# slave-relay-v1.net
KiCad netlist of a schematic drawn in EAGLE
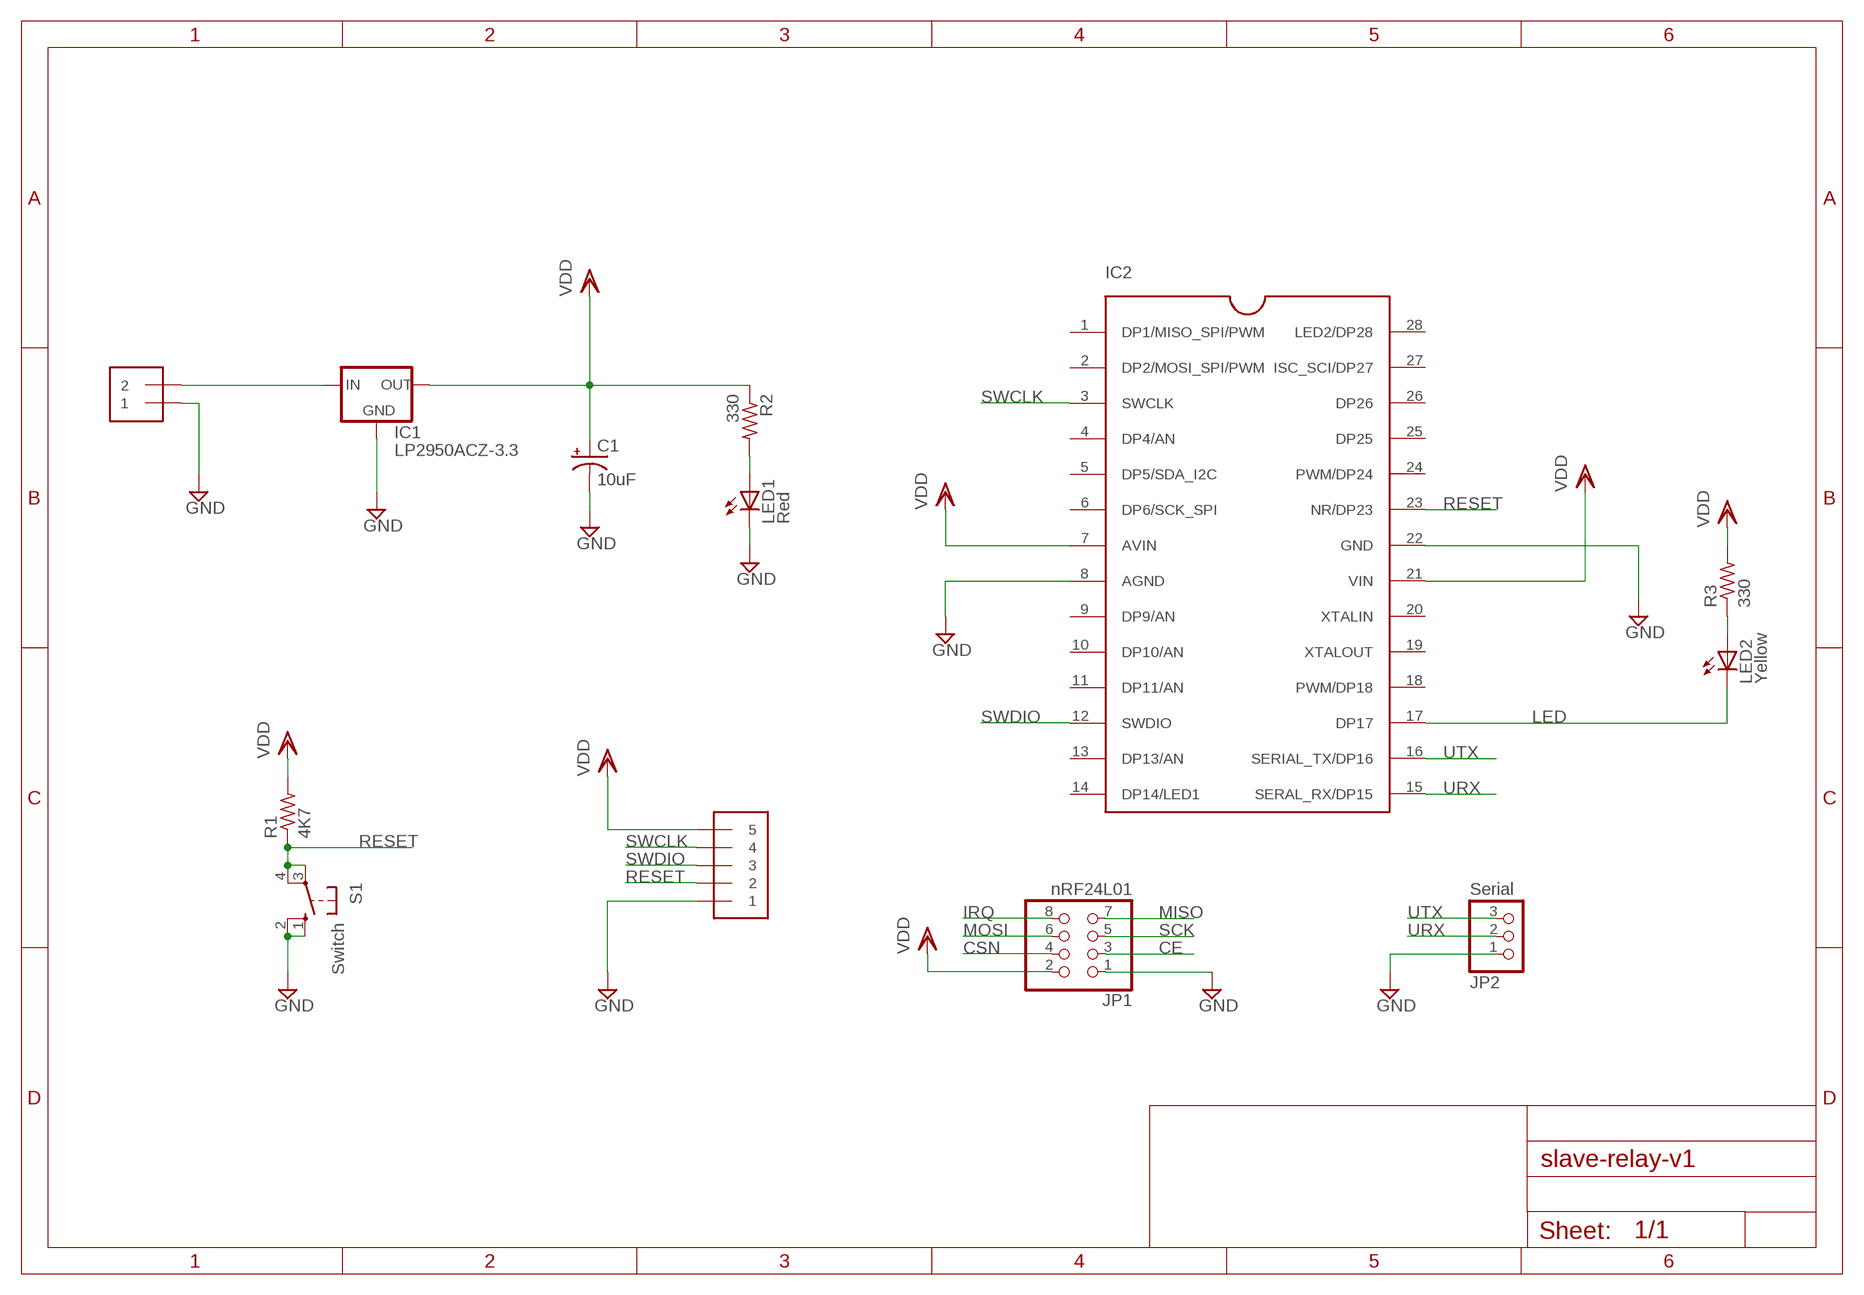
[diagram p0: schematic, sheet 1]

(export (version "E")
  (design (tool "Eeschema 10.0.6"))
  (components
    (comp (ref "C1")
      (value "10uF")
      (footprint "eagle-import:E2,5-7")
      (libsource (lib "eagle-import") (part "CPOL-USE2.5-7"))
    )
    (comp (ref "IC1")
      (value "LP2950ACZ-3.3")
      (footprint "eagle-import:TO92")
      (libsource (lib "eagle-import") (part "LP2950?ACZ-3.3"))
    )
    (comp (ref "IC2")
      (value "LPC1114FN28")
      (footprint "eagle-import:DIP28")
      (libsource (lib "eagle-import") (part "LPC1114FN28"))
    )
    (comp (ref "J1")
      (value "1X2-3.5MM")
      (footprint "eagle-import:1X2-3.5MM")
      (libsource (lib "eagle-import") (part "1X2-3.5MM"))
    )
    (comp (ref "J2")
      (value "SWD Debug")
      (footprint "eagle-import:1X05-3.5MM")
      (libsource (lib "eagle-import") (part "1X5"))
    )
    (comp (ref "JP1")
      (value "nRF24L01")
      (footprint "eagle-import:2X04")
      (libsource (lib "eagle-import") (part "PINHD-2X4"))
    )
    (comp (ref "JP2")
      (value "Serial")
      (footprint "eagle-import:1X03")
      (libsource (lib "eagle-import") (part "PINHD-1X3"))
    )
    (comp (ref "LED1")
      (value "Red")
      (footprint "eagle-import:LED5MM")
      (libsource (lib "eagle-import") (part "LED5MM"))
    )
    (comp (ref "LED2")
      (value "Yellow")
      (footprint "eagle-import:LED5MM")
      (libsource (lib "eagle-import") (part "LED5MM"))
    )
    (comp (ref "R1")
      (value "4K7")
      (footprint "eagle-import:0805-THM")
      (libsource (lib "eagle-import") (part "FLIPFLOP-RES"))
    )
    (comp (ref "R2")
      (value "330")
      (footprint "eagle-import:0805-THM")
      (libsource (lib "eagle-import") (part "FLIPFLOP-RES"))
    )
    (comp (ref "R3")
      (value "330")
      (footprint "eagle-import:0805-THM")
      (libsource (lib "eagle-import") (part "FLIPFLOP-RES"))
    )
    (comp (ref "S1")
      (value "Switch")
      (footprint "eagle-import:B3F-40XX")
      (fields (field (name "MF") "OMRON COMPONENTS USA") (field (name "MPN") "B3F-4000"))
      (libsource (lib "eagle-import") (part "40-XX"))
    )
  )
  (nets
    (net (code "1") (name "/CE") (class "Default")
      (node (ref "JP1") (pin "3") (pinfunction "3_3") (pintype "passive"))
    )
    (net (code "2") (name "/CSN") (class "Default")
      (node (ref "JP1") (pin "4") (pinfunction "4_4") (pintype "passive"))
    )
    (net (code "3") (name "/IRQ") (class "Default")
      (node (ref "JP1") (pin "8") (pinfunction "8_8") (pintype "passive"))
    )
    (net (code "4") (name "/LED") (class "Default")
      (node (ref "IC2") (pin "17") (pinfunction "DP17_17") (pintype "bidirectional"))
      (node (ref "LED2") (pin "K") (pinfunction "C_K") (pintype "passive"))
    )
    (net (code "5") (name "/MISO") (class "Default")
      (node (ref "JP1") (pin "7") (pinfunction "7_7") (pintype "passive"))
    )
    (net (code "6") (name "/MOSI") (class "Default")
      (node (ref "JP1") (pin "6") (pinfunction "6_6") (pintype "passive"))
    )
    (net (code "7") (name "/RESET") (class "Default")
      (node (ref "IC2") (pin "23") (pinfunction "NR/DP23_23") (pintype "bidirectional"))
      (node (ref "J2") (pin "2") (pinfunction "2_2") (pintype "passive"))
      (node (ref "R1") (pin "1") (pinfunction "1_1") (pintype "passive"))
      (node (ref "S1") (pin "3") (pinfunction "P_3") (pintype "passive"))
      (node (ref "S1") (pin "4") (pinfunction "P1_4") (pintype "passive"))
    )
    (net (code "8") (name "/SCK") (class "Default")
      (node (ref "JP1") (pin "5") (pinfunction "5_5") (pintype "passive"))
    )
    (net (code "9") (name "/SWCLK") (class "Default")
      (node (ref "IC2") (pin "3") (pinfunction "SWCLK_3") (pintype "bidirectional"))
      (node (ref "J2") (pin "4") (pinfunction "4_4") (pintype "passive"))
    )
    (net (code "10") (name "/SWDIO") (class "Default")
      (node (ref "IC2") (pin "12") (pinfunction "SWDIO_12") (pintype "bidirectional"))
      (node (ref "J2") (pin "3") (pinfunction "3_3") (pintype "passive"))
    )
    (net (code "11") (name "/URX") (class "Default")
      (node (ref "IC2") (pin "15") (pinfunction "SERAL_RX/DP15_15") (pintype "bidirectional"))
      (node (ref "JP2") (pin "2") (pinfunction "2_2") (pintype "passive"))
    )
    (net (code "12") (name "/UTX") (class "Default")
      (node (ref "IC2") (pin "16") (pinfunction "SERIAL_TX/DP16_16") (pintype "bidirectional"))
      (node (ref "JP2") (pin "3") (pinfunction "3_3") (pintype "passive"))
    )
    (net (code "13") (name "GND") (class "Default")
      (node (ref "C1") (pin "-") (pinfunction "-_-") (pintype "passive"))
      (node (ref "IC1") (pin "2") (pinfunction "GND_2") (pintype "input"))
      (node (ref "IC2") (pin "22") (pinfunction "GND_22") (pintype "power_in"))
      (node (ref "IC2") (pin "8") (pinfunction "AGND_8") (pintype "power_in"))
      (node (ref "J1") (pin "1") (pinfunction "1_1") (pintype "passive"))
      (node (ref "J2") (pin "1") (pinfunction "1_1") (pintype "passive"))
      (node (ref "JP1") (pin "1") (pinfunction "1_1") (pintype "passive"))
      (node (ref "JP2") (pin "1") (pinfunction "1_1") (pintype "passive"))
      (node (ref "LED1") (pin "K") (pinfunction "C_K") (pintype "passive"))
      (node (ref "S1") (pin "1") (pinfunction "S_1") (pintype "passive"))
      (node (ref "S1") (pin "2") (pinfunction "S1_2") (pintype "passive"))
    )
    (net (code "14") (name "Net-(IC1-IN)") (class "Default")
      (node (ref "IC1") (pin "3") (pinfunction "IN_3") (pintype "input"))
      (node (ref "J1") (pin "2") (pinfunction "2_2") (pintype "passive"))
    )
    (net (code "15") (name "Net-(LED1-PadA)") (class "Default")
      (node (ref "LED1") (pin "A") (pinfunction "A_A") (pintype "passive"))
      (node (ref "R2") (pin "2") (pinfunction "2_2") (pintype "passive"))
    )
    (net (code "16") (name "Net-(LED2-PadA)") (class "Default")
      (node (ref "LED2") (pin "A") (pinfunction "A_A") (pintype "passive"))
      (node (ref "R3") (pin "1") (pinfunction "1_1") (pintype "passive"))
    )
    (net (code "17") (name "VDD") (class "Default")
      (node (ref "C1") (pin "+") (pinfunction "+_+") (pintype "passive"))
      (node (ref "IC1") (pin "1") (pinfunction "OUT_1") (pintype "passive"))
      (node (ref "IC2") (pin "21") (pinfunction "VIN_21") (pintype "power_in"))
      (node (ref "IC2") (pin "7") (pinfunction "AVIN_7") (pintype "power_in"))
      (node (ref "J2") (pin "5") (pinfunction "5_5") (pintype "passive"))
      (node (ref "JP1") (pin "2") (pinfunction "2_2") (pintype "passive"))
      (node (ref "R1") (pin "2") (pinfunction "2_2") (pintype "passive"))
      (node (ref "R2") (pin "1") (pinfunction "1_1") (pintype "passive"))
      (node (ref "R3") (pin "2") (pinfunction "2_2") (pintype "passive"))
    )
    (net (code "18") (name "unconnected-(IC2-DP1{slash}MISO_SPI{slash}PWM-Pad1)") (class "Default")
      (node (ref "IC2") (pin "1") (pinfunction "DP1/MISO_SPI/PWM_1") (pintype "bidirectional"))
    )
    (net (code "19") (name "unconnected-(IC2-DP2{slash}MOSI_SPI{slash}PWM-Pad2)") (class "Default")
      (node (ref "IC2") (pin "2") (pinfunction "DP2/MOSI_SPI/PWM_2") (pintype "bidirectional"))
    )
    (net (code "20") (name "unconnected-(IC2-DP4{slash}AN-Pad4)") (class "Default")
      (node (ref "IC2") (pin "4") (pinfunction "DP4/AN_4") (pintype "bidirectional"))
    )
    (net (code "21") (name "unconnected-(IC2-DP5{slash}SDA_I2C-Pad5)") (class "Default")
      (node (ref "IC2") (pin "5") (pinfunction "DP5/SDA_I2C_5") (pintype "bidirectional"))
    )
    (net (code "22") (name "unconnected-(IC2-DP6{slash}SCK_SPI-Pad6)") (class "Default")
      (node (ref "IC2") (pin "6") (pinfunction "DP6/SCK_SPI_6") (pintype "bidirectional"))
    )
    (net (code "23") (name "unconnected-(IC2-DP9{slash}AN-Pad9)") (class "Default")
      (node (ref "IC2") (pin "9") (pinfunction "DP9/AN_9") (pintype "bidirectional"))
    )
    (net (code "24") (name "unconnected-(IC2-DP10{slash}AN-Pad10)") (class "Default")
      (node (ref "IC2") (pin "10") (pinfunction "DP10/AN_10") (pintype "bidirectional"))
    )
    (net (code "25") (name "unconnected-(IC2-DP11{slash}AN-Pad11)") (class "Default")
      (node (ref "IC2") (pin "11") (pinfunction "DP11/AN_11") (pintype "bidirectional"))
    )
    (net (code "26") (name "unconnected-(IC2-DP13{slash}AN-Pad13)") (class "Default")
      (node (ref "IC2") (pin "13") (pinfunction "DP13/AN_13") (pintype "bidirectional"))
    )
    (net (code "27") (name "unconnected-(IC2-DP14{slash}LED1-Pad14)") (class "Default")
      (node (ref "IC2") (pin "14") (pinfunction "DP14/LED1_14") (pintype "bidirectional"))
    )
    (net (code "28") (name "unconnected-(IC2-DP25-Pad25)") (class "Default")
      (node (ref "IC2") (pin "25") (pinfunction "DP25_25") (pintype "bidirectional"))
    )
    (net (code "29") (name "unconnected-(IC2-DP26-Pad26)") (class "Default")
      (node (ref "IC2") (pin "26") (pinfunction "DP26_26") (pintype "bidirectional"))
    )
    (net (code "30") (name "unconnected-(IC2-ISC_SCI{slash}DP27-Pad27)") (class "Default")
      (node (ref "IC2") (pin "27") (pinfunction "ISC_SCI/DP27_27") (pintype "bidirectional"))
    )
    (net (code "31") (name "unconnected-(IC2-LED2{slash}DP28-Pad28)") (class "Default")
      (node (ref "IC2") (pin "28") (pinfunction "LED2/DP28_28") (pintype "bidirectional"))
    )
    (net (code "32") (name "unconnected-(IC2-PWM{slash}DP18-Pad18)") (class "Default")
      (node (ref "IC2") (pin "18") (pinfunction "PWM/DP18_18") (pintype "bidirectional"))
    )
    (net (code "33") (name "unconnected-(IC2-PWM{slash}DP24-Pad24)") (class "Default")
      (node (ref "IC2") (pin "24") (pinfunction "PWM/DP24_24") (pintype "bidirectional"))
    )
    (net (code "34") (name "unconnected-(IC2-XTALIN-Pad20)") (class "Default")
      (node (ref "IC2") (pin "20") (pinfunction "XTALIN_20") (pintype "input"))
    )
    (net (code "35") (name "unconnected-(IC2-XTALOUT-Pad19)") (class "Default")
      (node (ref "IC2") (pin "19") (pinfunction "XTALOUT_19") (pintype "output"))
    )
  )
)
